# drawerlights.net
KiCad netlist of a schematic drawn in EAGLE
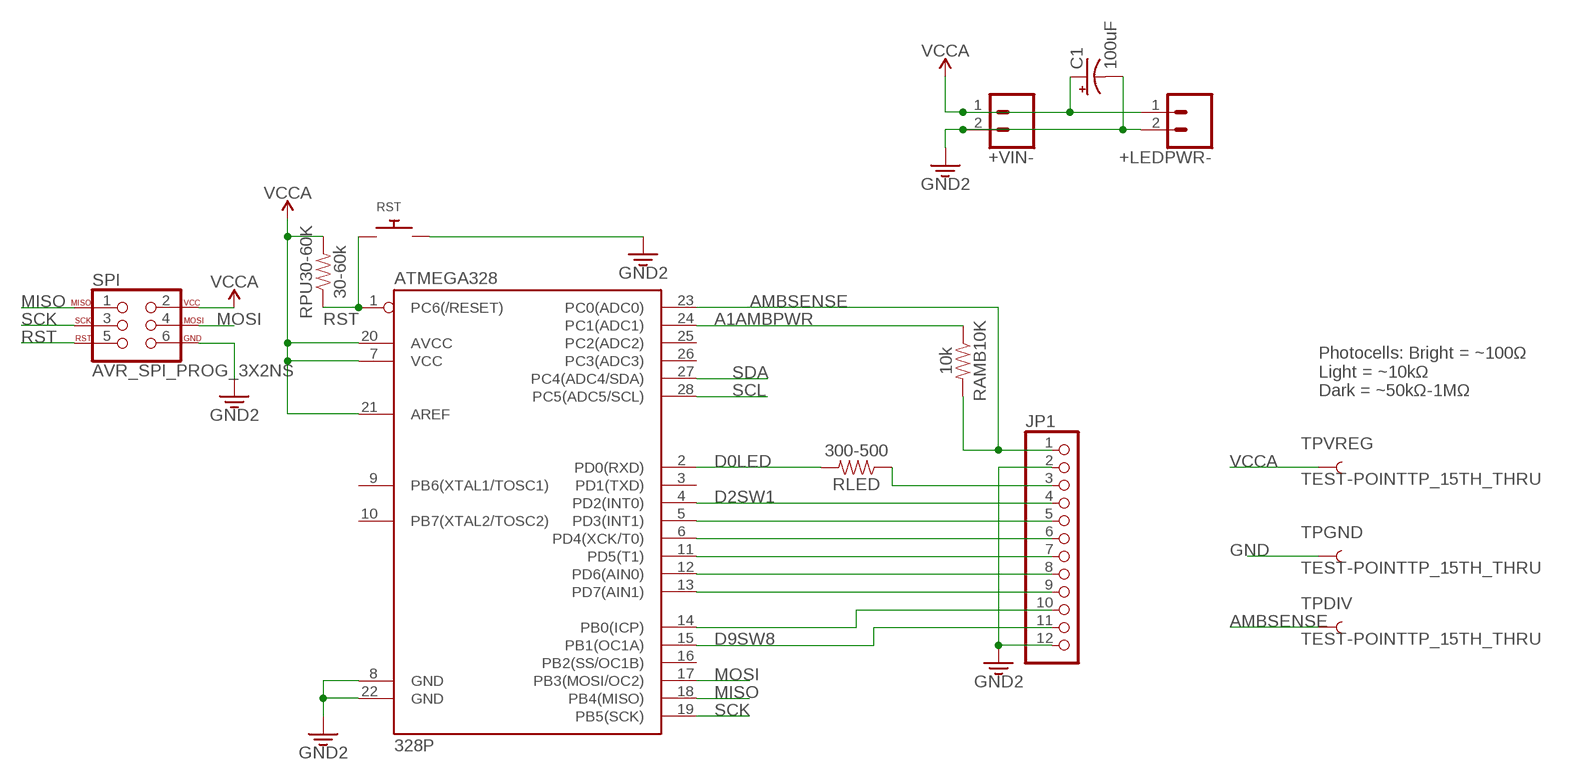
[diagram p0: schematic, sheet 1]

(export (version "E")
  (design (tool "Eeschema 10.0.6"))
  (components
    (comp (ref "+LEDPWR-")
      (value "CONN_02")
      (footprint "eagle-import:1X02")
      (libsource (lib "eagle-import") (part "CONN_02"))
    )
    (comp (ref "+VIN-")
      (value "CONN_02")
      (footprint "eagle-import:1X02")
      (libsource (lib "eagle-import") (part "CONN_02"))
    )
    (comp (ref "ATMEGA328")
      (value "328P")
      (footprint "eagle-import:DIP28")
      (libsource (lib "eagle-import") (part "ATMEGA328P_PDIP"))
    )
    (comp (ref "C1")
      (value "100uF")
      (footprint "eagle-import:CPOL-RADIAL-2.5MM-6.5MM")
      (libsource (lib "eagle-import") (part "100UF-POLAR-RADIAL-2.5MM-25V-20%"))
    )
    (comp (ref "JP1")
      (value "PINHD-1X12-CB")
      (footprint "eagle-import:1X12-CB")
      (libsource (lib "eagle-import") (part "PINHD-1X12-CB"))
    )
    (comp (ref "RAMB10K")
      (value "10k")
      (footprint "eagle-import:AXIAL-0.3")
      (libsource (lib "eagle-import") (part "10KOHM-HORIZ-1/4W-1%"))
    )
    (comp (ref "RLED")
      (value "300-500")
      (footprint "eagle-import:AXIAL-0.3")
      (libsource (lib "eagle-import") (part "330OHM-HORIZ-1/10W-5%"))
    )
    (comp (ref "RPU30-60K")
      (value "30-60k")
      (footprint "eagle-import:AXIAL-0.3")
      (libsource (lib "eagle-import") (part "330OHM-HORIZ-1/10W-5%"))
    )
    (comp (ref "RST")
      (value "SWITCH_PUSHBUTTONEVQ-PE")
      (footprint "eagle-import:TACT_PANA-EVQ")
      (libsource (lib "eagle-import") (part "SWITCH_PUSHBUTTONEVQ-PE"))
    )
    (comp (ref "SPI")
      (value "AVR_SPI_PROG_3X2NS")
      (footprint "eagle-import:2X3-NS")
      (libsource (lib "eagle-import") (part "AVR_SPI_PROG_3X2NS"))
    )
    (comp (ref "TPDIV")
      (value "TEST-POINTTP_15TH_THRU")
      (footprint "eagle-import:TP_15TH")
      (libsource (lib "eagle-import") (part "TEST-POINTTP_15TH_THRU"))
    )
    (comp (ref "TPGND")
      (value "TEST-POINTTP_15TH_THRU")
      (footprint "eagle-import:TP_15TH")
      (libsource (lib "eagle-import") (part "TEST-POINTTP_15TH_THRU"))
    )
    (comp (ref "TPVREG")
      (value "TEST-POINTTP_15TH_THRU")
      (footprint "eagle-import:TP_15TH")
      (libsource (lib "eagle-import") (part "TEST-POINTTP_15TH_THRU"))
    )
  )
  (nets
    (net (code "1") (name "/A1AMBPWR") (class "Default")
      (node (ref "ATMEGA328") (pin "24") (pinfunction "PC1(ADC1)_24") (pintype "bidirectional"))
      (node (ref "RAMB10K") (pin "P$1") (pinfunction "1_P$1") (pintype "passive"))
    )
    (net (code "2") (name "/AMBSENSE") (class "Default")
      (node (ref "ATMEGA328") (pin "23") (pinfunction "PC0(ADC0)_23") (pintype "bidirectional"))
      (node (ref "JP1") (pin "1") (pinfunction "1_1") (pintype "passive"))
      (node (ref "RAMB10K") (pin "P$2") (pinfunction "2_P$2") (pintype "passive"))
      (node (ref "TPDIV") (pin "P$1") (pinfunction "1_P$1") (pintype "bidirectional"))
    )
    (net (code "3") (name "/D0LED") (class "Default")
      (node (ref "ATMEGA328") (pin "2") (pinfunction "PD0(RXD)_2") (pintype "bidirectional"))
      (node (ref "RLED") (pin "P$2") (pinfunction "2_P$2") (pintype "passive"))
    )
    (net (code "4") (name "/D2SW1") (class "Default")
      (node (ref "ATMEGA328") (pin "4") (pinfunction "PD2(INT0)_4") (pintype "bidirectional"))
      (node (ref "JP1") (pin "4") (pinfunction "4_4") (pintype "passive"))
    )
    (net (code "5") (name "/D9SW8") (class "Default")
      (node (ref "ATMEGA328") (pin "15") (pinfunction "PB1(OC1A)_15") (pintype "bidirectional"))
      (node (ref "JP1") (pin "11") (pinfunction "11_11") (pintype "passive"))
    )
    (net (code "6") (name "/MISO") (class "Default")
      (node (ref "ATMEGA328") (pin "18") (pinfunction "PB4(MISO)_18") (pintype "bidirectional"))
      (node (ref "SPI") (pin "1") (pinfunction "1_1") (pintype "passive"))
    )
    (net (code "7") (name "/MOSI") (class "Default")
      (node (ref "ATMEGA328") (pin "17") (pinfunction "PB3(MOSI/OC2)_17") (pintype "bidirectional"))
      (node (ref "SPI") (pin "4") (pinfunction "4_4") (pintype "passive"))
    )
    (net (code "8") (name "/RST") (class "Default")
      (node (ref "ATMEGA328") (pin "1") (pinfunction "PC6(/RESET)_1") (pintype "bidirectional"))
      (node (ref "RPU30-60K") (pin "P$1") (pinfunction "1_P$1") (pintype "passive"))
      (node (ref "RST") (pin "P$1") (pinfunction "P$1_P$1") (pintype "passive"))
      (node (ref "SPI") (pin "5") (pinfunction "5_5") (pintype "passive"))
    )
    (net (code "9") (name "/SCK") (class "Default")
      (node (ref "ATMEGA328") (pin "19") (pinfunction "PB5(SCK)_19") (pintype "bidirectional"))
      (node (ref "SPI") (pin "3") (pinfunction "3_3") (pintype "passive"))
    )
    (net (code "10") (name "/SCL") (class "Default")
      (node (ref "ATMEGA328") (pin "28") (pinfunction "PC5(ADC5/SCL)_28") (pintype "bidirectional"))
    )
    (net (code "11") (name "/SDA") (class "Default")
      (node (ref "ATMEGA328") (pin "27") (pinfunction "PC4(ADC4/SDA)_27") (pintype "bidirectional"))
    )
    (net (code "12") (name "GND2") (class "Default")
      (node (ref "+LEDPWR-") (pin "2") (pinfunction "2_2") (pintype "passive"))
      (node (ref "+VIN-") (pin "2") (pinfunction "2_2") (pintype "passive"))
      (node (ref "ATMEGA328") (pin "22") (pinfunction "GND_22") (pintype "bidirectional"))
      (node (ref "ATMEGA328") (pin "8") (pinfunction "GND_8") (pintype "bidirectional"))
      (node (ref "C1") (pin "2") (pinfunction "-_2") (pintype "passive"))
      (node (ref "JP1") (pin "12") (pinfunction "12_12") (pintype "passive"))
      (node (ref "JP1") (pin "2") (pinfunction "2_2") (pintype "passive"))
      (node (ref "RST") (pin "P$2") (pinfunction "P$2_P$2") (pintype "passive"))
      (node (ref "SPI") (pin "6") (pinfunction "6_6") (pintype "passive"))
      (node (ref "TPGND") (pin "P$1") (pinfunction "1_P$1") (pintype "bidirectional"))
    )
    (net (code "13") (name "Net-(ATMEGA328-PB0(ICP))") (class "Default")
      (node (ref "ATMEGA328") (pin "14") (pinfunction "PB0(ICP)_14") (pintype "bidirectional"))
      (node (ref "JP1") (pin "10") (pinfunction "10_10") (pintype "passive"))
    )
    (net (code "14") (name "Net-(ATMEGA328-PD3(INT1))") (class "Default")
      (node (ref "ATMEGA328") (pin "5") (pinfunction "PD3(INT1)_5") (pintype "bidirectional"))
      (node (ref "JP1") (pin "5") (pinfunction "5_5") (pintype "passive"))
    )
    (net (code "15") (name "Net-(ATMEGA328-PD4(XCK{slash}T0))") (class "Default")
      (node (ref "ATMEGA328") (pin "6") (pinfunction "PD4(XCK/T0)_6") (pintype "bidirectional"))
      (node (ref "JP1") (pin "6") (pinfunction "6_6") (pintype "passive"))
    )
    (net (code "16") (name "Net-(ATMEGA328-PD5(T1))") (class "Default")
      (node (ref "ATMEGA328") (pin "11") (pinfunction "PD5(T1)_11") (pintype "bidirectional"))
      (node (ref "JP1") (pin "7") (pinfunction "7_7") (pintype "passive"))
    )
    (net (code "17") (name "Net-(ATMEGA328-PD6(AIN0))") (class "Default")
      (node (ref "ATMEGA328") (pin "12") (pinfunction "PD6(AIN0)_12") (pintype "bidirectional"))
      (node (ref "JP1") (pin "8") (pinfunction "8_8") (pintype "passive"))
    )
    (net (code "18") (name "Net-(ATMEGA328-PD7(AIN1))") (class "Default")
      (node (ref "ATMEGA328") (pin "13") (pinfunction "PD7(AIN1)_13") (pintype "bidirectional"))
      (node (ref "JP1") (pin "9") (pinfunction "9_9") (pintype "passive"))
    )
    (net (code "19") (name "Net-(RLED-1)") (class "Default")
      (node (ref "JP1") (pin "3") (pinfunction "3_3") (pintype "passive"))
      (node (ref "RLED") (pin "P$1") (pinfunction "1_P$1") (pintype "passive"))
    )
    (net (code "20") (name "VCCA") (class "Default")
      (node (ref "+LEDPWR-") (pin "1") (pinfunction "1_1") (pintype "passive"))
      (node (ref "+VIN-") (pin "1") (pinfunction "1_1") (pintype "passive"))
      (node (ref "ATMEGA328") (pin "20") (pinfunction "AVCC_20") (pintype "bidirectional"))
      (node (ref "ATMEGA328") (pin "21") (pinfunction "AREF_21") (pintype "bidirectional"))
      (node (ref "ATMEGA328") (pin "7") (pinfunction "VCC_7") (pintype "bidirectional"))
      (node (ref "C1") (pin "1") (pinfunction "+_1") (pintype "passive"))
      (node (ref "RPU30-60K") (pin "P$2") (pinfunction "2_P$2") (pintype "passive"))
      (node (ref "SPI") (pin "2") (pinfunction "2_2") (pintype "passive"))
      (node (ref "TPVREG") (pin "P$1") (pinfunction "1_P$1") (pintype "bidirectional"))
    )
    (net (code "21") (name "unconnected-(ATMEGA328-PB2(SS{slash}OC1B)-Pad16)") (class "Default")
      (node (ref "ATMEGA328") (pin "16") (pinfunction "PB2(SS/OC1B)_16") (pintype "bidirectional"))
    )
    (net (code "22") (name "unconnected-(ATMEGA328-PB6(XTAL1{slash}TOSC1)-Pad9)") (class "Default")
      (node (ref "ATMEGA328") (pin "9") (pinfunction "PB6(XTAL1/TOSC1)_9") (pintype "bidirectional"))
    )
    (net (code "23") (name "unconnected-(ATMEGA328-PB7(XTAL2{slash}TOSC2)-Pad10)") (class "Default")
      (node (ref "ATMEGA328") (pin "10") (pinfunction "PB7(XTAL2/TOSC2)_10") (pintype "bidirectional"))
    )
    (net (code "24") (name "unconnected-(ATMEGA328-PC2(ADC2)-Pad25)") (class "Default")
      (node (ref "ATMEGA328") (pin "25") (pinfunction "PC2(ADC2)_25") (pintype "bidirectional"))
    )
    (net (code "25") (name "unconnected-(ATMEGA328-PC3(ADC3)-Pad26)") (class "Default")
      (node (ref "ATMEGA328") (pin "26") (pinfunction "PC3(ADC3)_26") (pintype "bidirectional"))
    )
    (net (code "26") (name "unconnected-(ATMEGA328-PD1(TXD)-Pad3)") (class "Default")
      (node (ref "ATMEGA328") (pin "3") (pinfunction "PD1(TXD)_3") (pintype "bidirectional"))
    )
  )
)
